# reflow.net
KiCad netlist of a schematic drawn in Altium Designer
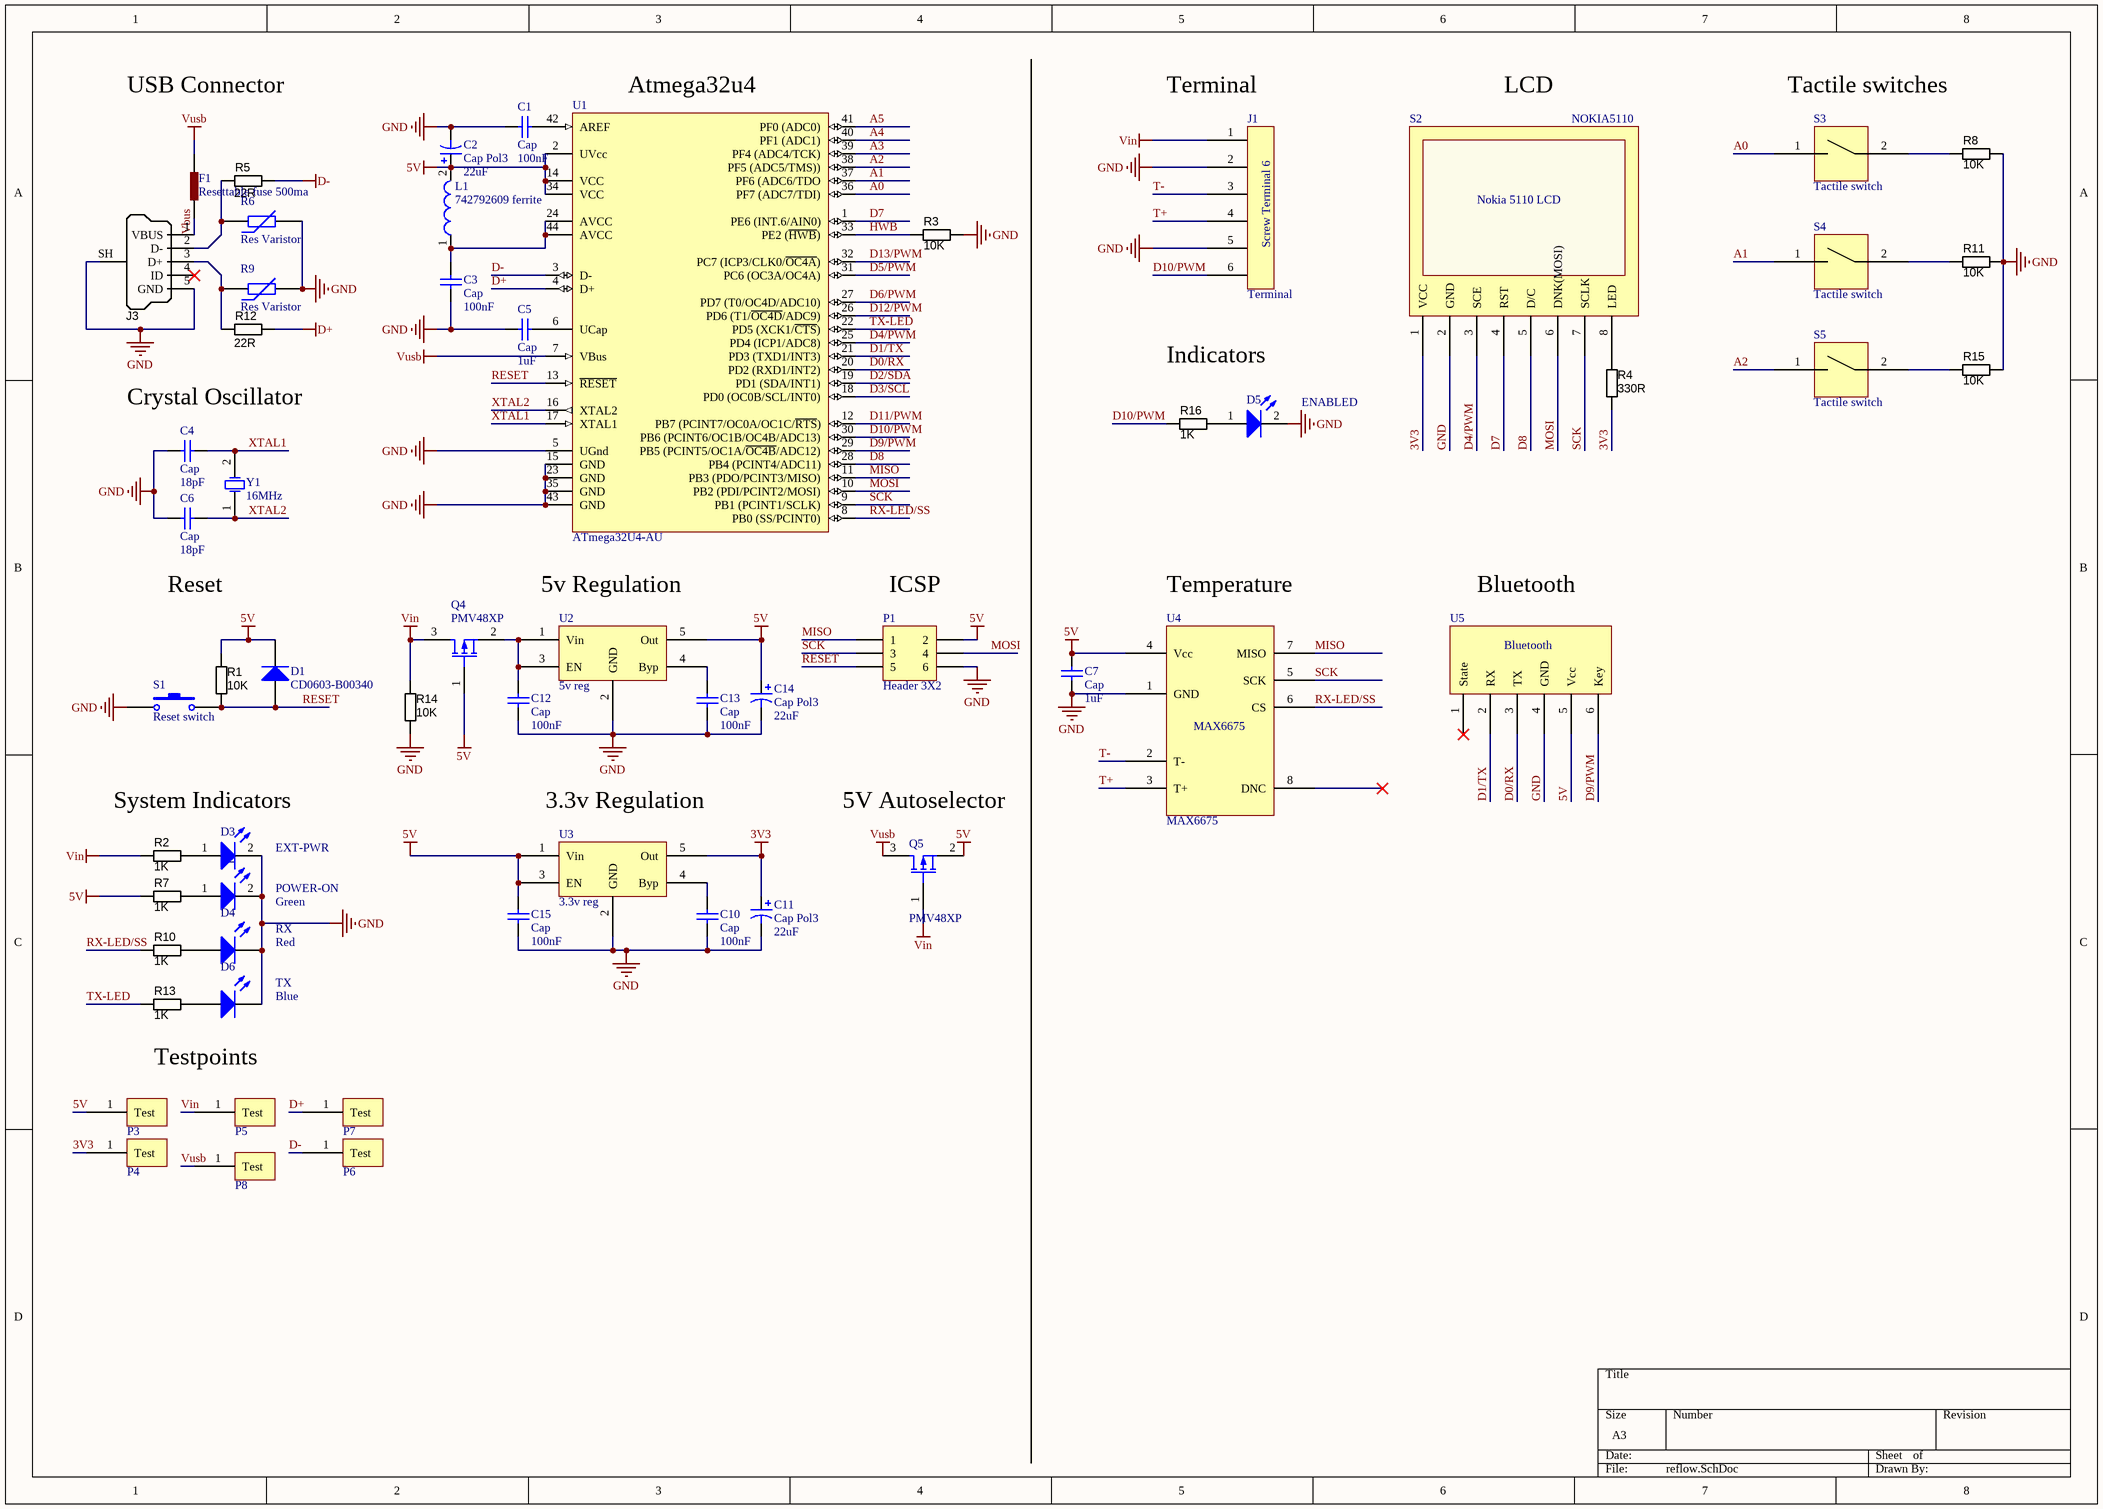
[diagram p0: reflow.SchDoc]

(export (version "E")
  (design (tool "Eeschema 10.0.6"))
  (components
    (comp (ref "C1")
      (value "Cap")
      (footprint "CAP-0603-GEN")
      (description "Capacitor")
      (fields (field (name "ALTIUM_VALUE") "100nF") (field (name "PUBLISHER") "Altium Limited"))
      (libsource (lib "Miscellaneous Devices") (part "Cap"))
    )
    (comp (ref "C2")
      (value "Cap Pol3")
      (footprint "CAP-0603-POL")
      (description "Polarized Capacitor (Surface Mount)")
      (fields (field (name "ALTIUM_VALUE") "22uF") (field (name "PUBLISHER") "Altium Limited"))
      (libsource (lib "Miscellaneous Devices") (part "Cap Pol3"))
    )
    (comp (ref "C3")
      (value "Cap")
      (footprint "CAP-0603-GEN")
      (description "Capacitor")
      (fields (field (name "ALTIUM_VALUE") "100nF") (field (name "PUBLISHER") "Altium Limited"))
      (libsource (lib "Miscellaneous Devices") (part "Cap"))
    )
    (comp (ref "C4")
      (value "Cap")
      (footprint "CAP-0603-GEN")
      (description "Capacitor")
      (fields (field (name "ALTIUM_VALUE") "18pF") (field (name "PUBLISHER") "Altium Limited"))
      (libsource (lib "Miscellaneous Devices") (part "Cap"))
    )
    (comp (ref "C5")
      (value "Cap")
      (footprint "CAP-0603-GEN")
      (description "Capacitor")
      (fields (field (name "ALTIUM_VALUE") "1uF") (field (name "PUBLISHER") "Altium Limited"))
      (libsource (lib "Miscellaneous Devices") (part "Cap"))
    )
    (comp (ref "C6")
      (value "Cap")
      (footprint "CAP-0603-GEN")
      (description "Capacitor")
      (fields (field (name "ALTIUM_VALUE") "18pF") (field (name "PUBLISHER") "Altium Limited"))
      (libsource (lib "Miscellaneous Devices") (part "Cap"))
    )
    (comp (ref "C7")
      (value "Cap")
      (footprint "CAP-0603-GEN")
      (description "Capacitor")
      (fields (field (name "ALTIUM_VALUE") "1uF") (field (name "PUBLISHER") "Altium Limited"))
      (libsource (lib "Miscellaneous Devices") (part "Cap"))
    )
    (comp (ref "C10")
      (value "Cap")
      (footprint "CAP-0603-GEN")
      (description "Capacitor")
      (fields (field (name "ALTIUM_VALUE") "100nF") (field (name "PUBLISHER") "Altium Limited"))
      (libsource (lib "Miscellaneous Devices") (part "Cap"))
    )
    (comp (ref "C11")
      (value "Cap Pol3")
      (footprint "CAP-0603-POL")
      (description "Polarized Capacitor (Surface Mount)")
      (fields (field (name "ALTIUM_VALUE") "22uF") (field (name "PUBLISHER") "Altium Limited"))
      (libsource (lib "Miscellaneous Devices") (part "Cap Pol3"))
    )
    (comp (ref "C12")
      (value "Cap")
      (footprint "CAP-0603-GEN")
      (description "Capacitor")
      (fields (field (name "ALTIUM_VALUE") "100nF") (field (name "PUBLISHER") "Altium Limited"))
      (libsource (lib "Miscellaneous Devices") (part "Cap"))
    )
    (comp (ref "C13")
      (value "Cap")
      (footprint "CAP-0603-GEN")
      (description "Capacitor")
      (fields (field (name "ALTIUM_VALUE") "100nF") (field (name "PUBLISHER") "Altium Limited"))
      (libsource (lib "Miscellaneous Devices") (part "Cap"))
    )
    (comp (ref "C14")
      (value "Cap Pol3")
      (footprint "CAP-0603-POL")
      (description "Polarized Capacitor (Surface Mount)")
      (fields (field (name "ALTIUM_VALUE") "22uF") (field (name "PUBLISHER") "Altium Limited"))
      (libsource (lib "Miscellaneous Devices") (part "Cap Pol3"))
    )
    (comp (ref "C15")
      (value "Cap")
      (footprint "CAP-0603-GEN")
      (description "Capacitor")
      (fields (field (name "ALTIUM_VALUE") "100nF") (field (name "PUBLISHER") "Altium Limited"))
      (libsource (lib "Miscellaneous Devices") (part "Cap"))
    )
    (comp (ref "D1")
      (value "CD0603-B00340")
      (footprint "DIODE-0603")
      (description "Default Diode")
      (fields (field (name "PUBLISHER") "Altium Limited"))
      (libsource (lib "Miscellaneous Devices") (part "Diode"))
    )
    (comp (ref "D2")
      (value "POWER-ON")
      (footprint "LED-0603")
      (description "Typical RED, GREEN, YELLOW, AMBER GaAs LED")
      (fields (field (name "PUBLISHER") "Altium Limited"))
      (libsource (lib "") (part "LED2_1"))
    )
    (comp (ref "D3")
      (value "EXT-PWR")
      (footprint "LED-0603")
      (description "Typical RED, GREEN, YELLOW, AMBER GaAs LED")
      (fields (field (name "PUBLISHER") "Altium Limited"))
      (libsource (lib "") (part "LED2_1"))
    )
    (comp (ref "D4")
      (value "RX")
      (footprint "LED-0603")
      (description "Typical RED, GREEN, YELLOW, AMBER GaAs LED")
      (fields (field (name "PUBLISHER") "Altium Limited"))
      (libsource (lib "Miscellaneous Devices") (part "LED2"))
    )
    (comp (ref "D5")
      (value "ENABLED")
      (footprint "LED-0603")
      (description "Typical RED, GREEN, YELLOW, AMBER GaAs LED")
      (fields (field (name "PUBLISHER") "Altium Limited"))
      (libsource (lib "") (part "LED2_1"))
    )
    (comp (ref "D6")
      (value "TX")
      (footprint "LED-0603")
      (description "Typical RED, GREEN, YELLOW, AMBER GaAs LED")
      (fields (field (name "PUBLISHER") "Altium Limited"))
      (libsource (lib "Miscellaneous Devices") (part "LED2"))
    )
    (comp (ref "F1")
      (value "Resettable fuse 500ma")
      (footprint "FUSE-0603")
      (description "Bourns resettable fuse")
      (libsource (lib "Bourns") (part "MF-MSMF"))
    )
    (comp (ref "J1")
      (value "Terminal")
      (footprint "HEADER-3x2-RIGHT")
      (description "Screw terminal")
      (libsource (lib "misc") (part "SCREW-TERMINAL-6"))
    )
    (comp (ref "J3")
      (value "USB Micro Type B (recommended if hand soldering)")
      (footprint "USB-MICRO-B")
      (description "Connector SMD-THD USB Micro Type B middle mount")
      (libsource (lib "PBL - Connectors") (part "USB_Micro_TypeB_FCI"))
    )
    (comp (ref "L1")
      (value "742792609 ferrite")
      (footprint "CAP-0603-GEN")
      (description "SMD EMI Suppression Ferrite Bead WE-CBF, Z = 30 Ohm")
      (libsource (lib "Wuerth Elektronik EMC Ferrite") (part "742792609"))
    )
    (comp (ref "P1")
      (value "Header 3X2")
      (footprint "TAG-CONNECT")
      (description "Header, 3-Pin, Dual row")
      (fields (field (name "PUBLISHER") "Altium Limited"))
      (libsource (lib "Miscellaneous Connectors") (part "Header 3X2"))
    )
    (comp (ref "P3") (value "TESTPOINT") (footprint "Testpoint") (libsource (lib "misc") (part "TESTPOINT")))
    (comp (ref "P4") (value "TESTPOINT") (footprint "Testpoint") (libsource (lib "misc") (part "TESTPOINT")))
    (comp (ref "P5") (value "TESTPOINT") (footprint "Testpoint") (libsource (lib "misc") (part "TESTPOINT")))
    (comp (ref "P6") (value "TESTPOINT") (footprint "Testpoint") (libsource (lib "misc") (part "TESTPOINT")))
    (comp (ref "P7") (value "TESTPOINT") (footprint "Testpoint") (libsource (lib "misc") (part "TESTPOINT")))
    (comp (ref "P8") (value "TESTPOINT") (footprint "Testpoint") (libsource (lib "misc") (part "TESTPOINT")))
    (comp (ref "Q4")
      (value "PMV48XP")
      (footprint "SOT23-3")
      (description "P-Channel MOSFET")
      (fields (field (name "PUBLISHER") "Altium Limited"))
      (libsource (lib "Miscellaneous Devices") (part "MOSFET-P"))
    )
    (comp (ref "Q5")
      (value "PMV48XP")
      (footprint "SOT23-3")
      (description "P-Channel MOSFET")
      (fields (field (name "PUBLISHER") "Altium Limited"))
      (libsource (lib "Miscellaneous Devices") (part "MOSFET-P"))
    )
    (comp (ref "R1")
      (value "10K")
      (footprint "RES-0603")
      (description "Resistor SMD chip 820 Ohm 0.1W 1% 0603")
      (fields (field (name "TOLERANCE") "±1%") (field (name "Comment") "Thick Film"))
      (libsource (lib "PBL - Resistors") (part "RES_820R_0603_1%"))
    )
    (comp (ref "R2")
      (value "1K")
      (footprint "RES-0603")
      (description "Resistor SMD chip 820 Ohm 0.1W 1% 0603")
      (fields (field (name "TOLERANCE") "±1%") (field (name "Comment") "Thick Film"))
      (libsource (lib "") (part "RES_820R_0603_1%_1"))
    )
    (comp (ref "R3")
      (value "10K")
      (footprint "RES-0603")
      (description "Resistor SMD chip 820 Ohm 0.1W 1% 0603")
      (fields (field (name "TOLERANCE") "±1%") (field (name "Comment") "Thick Film"))
      (libsource (lib "") (part "RES_820R_0603_1%_1"))
    )
    (comp (ref "R4")
      (value "330R")
      (footprint "RES-0603")
      (description "Resistor SMD chip 820 Ohm 0.1W 1% 0603")
      (fields (field (name "TOLERANCE") "±1%") (field (name "Comment") "Thick Film"))
      (libsource (lib "") (part "RES_820R_0603_1%_3"))
    )
    (comp (ref "R5")
      (value "22R")
      (footprint "RES-0603")
      (description "Resistor SMD chip 820 Ohm 0.1W 1% 0603")
      (fields (field (name "TOLERANCE") "±1%") (field (name "Comment") "Thick Film"))
      (libsource (lib "") (part "RES_820R_0603_1%_2"))
    )
    (comp (ref "R6")
      (value "Res Varistor")
      (footprint "RES-0603")
      (description "Varistor (Voltage-Sensitive Resistor)")
      (fields (field (name "PUBLISHER") "Altium Limited"))
      (libsource (lib "Miscellaneous Devices") (part "Res Varistor"))
    )
    (comp (ref "R7")
      (value "1K")
      (footprint "RES-0603")
      (description "Resistor SMD chip 820 Ohm 0.1W 1% 0603")
      (fields (field (name "TOLERANCE") "±1%") (field (name "Comment") "Thick Film"))
      (libsource (lib "") (part "RES_820R_0603_1%_1"))
    )
    (comp (ref "R8")
      (value "10K")
      (footprint "RES-0603")
      (description "Resistor SMD chip 820 Ohm 0.1W 1% 0603")
      (fields (field (name "TOLERANCE") "±1%") (field (name "Comment") "Thick Film"))
      (libsource (lib "") (part "RES_820R_0603_1%_1"))
    )
    (comp (ref "R9")
      (value "Res Varistor")
      (footprint "RES-0603")
      (description "Varistor (Voltage-Sensitive Resistor)")
      (fields (field (name "PUBLISHER") "Altium Limited"))
      (libsource (lib "Miscellaneous Devices") (part "Res Varistor"))
    )
    (comp (ref "R10")
      (value "1K")
      (footprint "RES-0603")
      (description "Resistor SMD chip 820 Ohm 0.1W 1% 0603")
      (fields (field (name "TOLERANCE") "±1%") (field (name "Comment") "Thick Film"))
      (libsource (lib "") (part "RES_820R_0603_1%_1"))
    )
    (comp (ref "R11")
      (value "10K")
      (footprint "RES-0603")
      (description "Resistor SMD chip 820 Ohm 0.1W 1% 0603")
      (fields (field (name "TOLERANCE") "±1%") (field (name "Comment") "Thick Film"))
      (libsource (lib "") (part "RES_820R_0603_1%_1"))
    )
    (comp (ref "R12")
      (value "22R")
      (footprint "RES-0603")
      (description "Resistor SMD chip 820 Ohm 0.1W 1% 0603")
      (fields (field (name "TOLERANCE") "±1%") (field (name "Comment") "Thick Film"))
      (libsource (lib "") (part "RES_820R_0603_1%_2"))
    )
    (comp (ref "R13")
      (value "1K")
      (footprint "RES-0603")
      (description "Resistor SMD chip 820 Ohm 0.1W 1% 0603")
      (fields (field (name "TOLERANCE") "±1%") (field (name "Comment") "Thick Film"))
      (libsource (lib "") (part "RES_820R_0603_1%_1"))
    )
    (comp (ref "R14")
      (value "10K")
      (footprint "RES-0603")
      (description "Resistor SMD chip 820 Ohm 0.1W 1% 0603")
      (fields (field (name "TOLERANCE") "±1%") (field (name "Comment") "Thick Film"))
      (libsource (lib "") (part "RES_820R_0603_1%_3"))
    )
    (comp (ref "R15")
      (value "10K")
      (footprint "RES-0603")
      (description "Resistor SMD chip 820 Ohm 0.1W 1% 0603")
      (fields (field (name "TOLERANCE") "±1%") (field (name "Comment") "Thick Film"))
      (libsource (lib "") (part "RES_820R_0603_1%_1"))
    )
    (comp (ref "R16")
      (value "1K")
      (footprint "RES-0603")
      (description "Resistor SMD chip 820 Ohm 0.1W 1% 0603")
      (fields (field (name "TOLERANCE") "±1%") (field (name "Comment") "Thick Film"))
      (libsource (lib "") (part "RES_820R_0603_1%_1"))
    )
    (comp (ref "S1")
      (value "Reset switch")
      (footprint "TACTILE-SWITCH")
      (description "Switch")
      (fields (field (name "PUBLISHER") "Altium Limited"))
      (libsource (lib "Miscellaneous Devices") (part "SW-PB"))
    )
    (comp (ref "S2") (value "NOKIA5110") (footprint "NOKIA5110") (libsource (lib "misc") (part "NOKIA5110")))
    (comp (ref "S3")
      (value "Tactile switch")
      (footprint "TACTILE-SWITCH")
      (libsource (lib "misc") (part "TACTILE-SWITCH-2"))
    )
    (comp (ref "S4")
      (value "Tactile switch")
      (footprint "TACTILE-SWITCH")
      (libsource (lib "misc") (part "TACTILE-SWITCH-2"))
    )
    (comp (ref "S5")
      (value "Tactile switch")
      (footprint "TACTILE-SWITCH")
      (libsource (lib "misc") (part "TACTILE-SWITCH-2"))
    )
    (comp (ref "U1")
      (value "ATmega32U4-AU")
      (footprint "44ML_N")
      (libsource (lib "Atmel Microcontroller megaAVR") (part "ATmega32U4-AU"))
    )
    (comp (ref "U2")
      (value "5v reg")
      (footprint "SOT23-5")
      (description "Voltage regulator")
      (libsource (lib "misc") (part "SOT23-REG"))
    )
    (comp (ref "U3")
      (value "3.3v reg")
      (footprint "SOT23-5")
      (description "Voltage regulator")
      (libsource (lib "misc") (part "SOT23-REG"))
    )
    (comp (ref "U4") (value "MAX6675") (footprint "SO8_N") (libsource (lib "misc") (part "MAX6675")))
    (comp (ref "U5")
      (value "Bluetooth module")
      (footprint "BLUETOOTH-MODULE")
      (libsource (lib "misc") (part "BLUETOOTH-MODULE"))
    )
    (comp (ref "Y1")
      (value "16MHz")
      (footprint "XTAL-5032")
      (description "Crystal Oscillator")
      (fields (field (name "PUBLISHER") "Altium Limited"))
      (libsource (lib "Miscellaneous Devices") (part "XTAL"))
    )
  )
  (nets
    (net (code "1") (name "/A0") (class "Default")
      (node (ref "S3") (pin "1") (pinfunction "1_1") (pintype "passive"))
      (node (ref "U1") (pin "36") (pinfunction "PF7_(ADC7/TDI)_36") (pintype "bidirectional"))
    )
    (net (code "2") (name "/A1") (class "Default")
      (node (ref "S4") (pin "1") (pinfunction "1_1") (pintype "passive"))
      (node (ref "U1") (pin "37") (pinfunction "PF6_(ADC6/TDO_37") (pintype "bidirectional"))
    )
    (net (code "3") (name "/A2") (class "Default")
      (node (ref "S5") (pin "1") (pinfunction "1_1") (pintype "passive"))
      (node (ref "U1") (pin "38") (pinfunction "PF5_(ADC5/TMS))_38") (pintype "bidirectional"))
    )
    (net (code "4") (name "/A3") (class "Default")
      (node (ref "U1") (pin "39") (pinfunction "PF4_(ADC4/TCK)_39") (pintype "bidirectional"))
    )
    (net (code "5") (name "/A4") (class "Default")
      (node (ref "U1") (pin "40") (pinfunction "PF1_(ADC1)_40") (pintype "bidirectional"))
    )
    (net (code "6") (name "/A5") (class "Default")
      (node (ref "U1") (pin "41") (pinfunction "PF0_(ADC0)_41") (pintype "bidirectional"))
    )
    (net (code "7") (name "/D0{slash}RX") (class "Default")
      (node (ref "U1") (pin "20") (pinfunction "PD2_(RXD1/INT2)_20") (pintype "bidirectional"))
      (node (ref "U5") (pin "3") (pinfunction "TX_3") (pintype "passive"))
    )
    (net (code "8") (name "/D1{slash}TX") (class "Default")
      (node (ref "U1") (pin "21") (pinfunction "PD3_(TXD1/INT3)_21") (pintype "bidirectional"))
      (node (ref "U5") (pin "2") (pinfunction "RX_2") (pintype "passive"))
    )
    (net (code "9") (name "/D2{slash}SDA") (class "Default")
      (node (ref "U1") (pin "19") (pinfunction "PD1_(SDA/INT1)_19") (pintype "bidirectional"))
    )
    (net (code "10") (name "/D3{slash}SCL") (class "Default")
      (node (ref "U1") (pin "18") (pinfunction "PD0_(OC0B/SCL/INT0)_18") (pintype "bidirectional"))
    )
    (net (code "11") (name "/D4{slash}PWM") (class "Default")
      (node (ref "S2") (pin "3") (pinfunction "SCE_3") (pintype "passive"))
      (node (ref "U1") (pin "25") (pinfunction "PD4_(ICP1/ADC8)_25") (pintype "bidirectional"))
    )
    (net (code "12") (name "/D5{slash}PWM") (class "Default")
      (node (ref "U1") (pin "31") (pinfunction "PC6_(OC3A/OC4A)_31") (pintype "bidirectional"))
    )
    (net (code "13") (name "/D6{slash}PWM") (class "Default")
      (node (ref "U1") (pin "27") (pinfunction "PD7_(T0/OC4D/ADC10)_27") (pintype "bidirectional"))
    )
    (net (code "14") (name "/D7") (class "Default")
      (node (ref "S2") (pin "4") (pinfunction "RST_4") (pintype "passive"))
      (node (ref "U1") (pin "1") (pinfunction "PE6_(INT.6/AIN0)_1") (pintype "bidirectional"))
    )
    (net (code "15") (name "/D8") (class "Default")
      (node (ref "S2") (pin "5") (pinfunction "D/C_5") (pintype "passive"))
      (node (ref "U1") (pin "28") (pinfunction "PB4_(PCINT4/ADC11)_28") (pintype "bidirectional"))
    )
    (net (code "16") (name "/D9{slash}PWM") (class "Default")
      (node (ref "U1") (pin "29") (pinfunction "PB5_(PCINT5/OC1A/~{OC4B}/ADC12)_29") (pintype "bidirectional"))
      (node (ref "U5") (pin "6") (pinfunction "Key_6") (pintype "passive"))
    )
    (net (code "17") (name "/D10{slash}PWM") (class "Default")
      (node (ref "J1") (pin "6") (pinfunction "6_6") (pintype "passive"))
      (node (ref "R16") (pin "2") (pinfunction "2_2") (pintype "passive"))
      (node (ref "U1") (pin "30") (pinfunction "PB6_(PCINT6/OC1B/OC4B/ADC13)_30") (pintype "bidirectional"))
    )
    (net (code "18") (name "/D11{slash}PWM") (class "Default")
      (node (ref "U1") (pin "12") (pinfunction "PB7_(PCINT7/OC0A/OC1C/~{RTS})_12") (pintype "bidirectional"))
    )
    (net (code "19") (name "/D12{slash}PWM") (class "Default")
      (node (ref "U1") (pin "26") (pinfunction "PD6_(T1/~{OC4D}/ADC9)_26") (pintype "bidirectional"))
    )
    (net (code "20") (name "/D13{slash}PWM") (class "Default")
      (node (ref "U1") (pin "32") (pinfunction "PC7_(ICP3/CLK0/~{OC4A})_32") (pintype "bidirectional"))
    )
    (net (code "21") (name "/HWB") (class "Default")
      (node (ref "R3") (pin "2") (pinfunction "2_2") (pintype "passive"))
      (node (ref "U1") (pin "33") (pinfunction "PE2_(~{HWB})_33") (pintype "bidirectional"))
    )
    (net (code "22") (name "/MISO") (class "Default")
      (node (ref "P1") (pin "1") (pinfunction "1_1") (pintype "passive"))
      (node (ref "U1") (pin "11") (pinfunction "PB3_(PDO/PCINT3/MISO)_11") (pintype "bidirectional"))
      (node (ref "U4") (pin "7") (pinfunction "MISO_7") (pintype "passive"))
    )
    (net (code "23") (name "/MOSI") (class "Default")
      (node (ref "P1") (pin "4") (pinfunction "4_4") (pintype "passive"))
      (node (ref "S2") (pin "6") (pinfunction "DNK(MOSI)_6") (pintype "passive"))
      (node (ref "U1") (pin "10") (pinfunction "PB2_(PDI/PCINT2/MOSI)_10") (pintype "bidirectional"))
    )
    (net (code "24") (name "/RESET") (class "Default")
      (node (ref "D1") (pin "1") (pinfunction "A_1") (pintype "passive"))
      (node (ref "P1") (pin "5") (pinfunction "5_5") (pintype "passive"))
      (node (ref "R1") (pin "1") (pinfunction "1_1") (pintype "passive"))
      (node (ref "S1") (pin "2") (pinfunction "2_2") (pintype "passive"))
      (node (ref "U1") (pin "13") (pinfunction "~{RESET}_13") (pintype "input"))
    )
    (net (code "25") (name "/RX-LED{slash}SS") (class "Default")
      (node (ref "R10") (pin "2") (pinfunction "2_2") (pintype "passive"))
      (node (ref "U1") (pin "8") (pinfunction "PB0_(SS/PCINT0)_8") (pintype "bidirectional"))
      (node (ref "U4") (pin "6") (pinfunction "CS_6") (pintype "passive"))
    )
    (net (code "26") (name "/SCK") (class "Default")
      (node (ref "P1") (pin "3") (pinfunction "3_3") (pintype "passive"))
      (node (ref "S2") (pin "7") (pinfunction "SCLK_7") (pintype "passive"))
      (node (ref "U1") (pin "9") (pinfunction "PB1_(PCINT1/SCLK)_9") (pintype "bidirectional"))
      (node (ref "U4") (pin "5") (pinfunction "SCK_5") (pintype "passive"))
    )
    (net (code "27") (name "/T+") (class "Default")
      (node (ref "J1") (pin "4") (pinfunction "4_4") (pintype "passive"))
      (node (ref "U4") (pin "3") (pinfunction "T+_3") (pintype "passive"))
    )
    (net (code "28") (name "/T-") (class "Default")
      (node (ref "J1") (pin "3") (pinfunction "3_3") (pintype "passive"))
      (node (ref "U4") (pin "2") (pinfunction "T-_2") (pintype "passive"))
    )
    (net (code "29") (name "/TX-LED") (class "Default")
      (node (ref "R13") (pin "2") (pinfunction "2_2") (pintype "passive"))
      (node (ref "U1") (pin "22") (pinfunction "PD5_(XCK1/~{CTS})_22") (pintype "bidirectional"))
    )
    (net (code "30") (name "/Vbus") (class "Default")
      (node (ref "F1") (pin "1") (pinfunction "1_1") (pintype "passive"))
      (node (ref "J3") (pin "1") (pinfunction "VBUS_1") (pintype "passive"))
    )
    (net (code "31") (name "/XTAL1") (class "Default")
      (node (ref "C4") (pin "1") (pinfunction "1_1") (pintype "passive"))
      (node (ref "U1") (pin "17") (pinfunction "XTAL1_17") (pintype "input"))
      (node (ref "Y1") (pin "2") (pinfunction "OSC2_2") (pintype "passive"))
    )
    (net (code "32") (name "/XTAL2") (class "Default")
      (node (ref "C6") (pin "1") (pinfunction "1_1") (pintype "passive"))
      (node (ref "U1") (pin "16") (pinfunction "XTAL2_16") (pintype "output"))
      (node (ref "Y1") (pin "1") (pinfunction "OSC1_1") (pintype "passive"))
    )
    (net (code "33") (name "3V3") (class "Default")
      (node (ref "C11") (pin "1") (pinfunction "1_1") (pintype "passive"))
      (node (ref "P4") (pin "1") (pinfunction "Test_1") (pintype "passive"))
      (node (ref "R4") (pin "2") (pinfunction "2_2") (pintype "passive"))
      (node (ref "S2") (pin "1") (pinfunction "VCC_1") (pintype "passive"))
      (node (ref "U3") (pin "5") (pinfunction "Out_5") (pintype "passive"))
    )
    (net (code "34") (name "5V") (class "Default")
      (node (ref "C14") (pin "1") (pinfunction "1_1") (pintype "passive"))
      (node (ref "C15") (pin "2") (pinfunction "2_2") (pintype "passive"))
      (node (ref "C2") (pin "1") (pinfunction "1_1") (pintype "passive"))
      (node (ref "C7") (pin "2") (pinfunction "2_2") (pintype "passive"))
      (node (ref "D1") (pin "2") (pinfunction "K_2") (pintype "passive"))
      (node (ref "L1") (pin "2") (pinfunction "2_2") (pintype "passive"))
      (node (ref "P1") (pin "2") (pinfunction "2_2") (pintype "passive"))
      (node (ref "P3") (pin "1") (pinfunction "Test_1") (pintype "passive"))
      (node (ref "Q4") (pin "1") (pinfunction "S_1") (pintype "passive"))
      (node (ref "Q5") (pin "2") (pinfunction "D_2") (pintype "passive"))
      (node (ref "R1") (pin "2") (pinfunction "2_2") (pintype "passive"))
      (node (ref "R7") (pin "2") (pinfunction "2_2") (pintype "passive"))
      (node (ref "U1") (pin "14") (pinfunction "VCC_14") (pintype "power_in"))
      (node (ref "U1") (pin "2") (pinfunction "UVcc_2") (pintype "power_in"))
      (node (ref "U1") (pin "34") (pinfunction "VCC_34") (pintype "power_in"))
      (node (ref "U2") (pin "5") (pinfunction "Out_5") (pintype "passive"))
      (node (ref "U3") (pin "1") (pinfunction "Vin_1") (pintype "passive"))
      (node (ref "U3") (pin "3") (pinfunction "EN_3") (pintype "passive"))
      (node (ref "U4") (pin "4") (pinfunction "Vcc_4") (pintype "passive"))
      (node (ref "U5") (pin "5") (pinfunction "Vcc_5") (pintype "passive"))
    )
    (net (code "35") (name "D+") (class "Default")
      (node (ref "P7") (pin "1") (pinfunction "Test_1") (pintype "passive"))
      (node (ref "R12") (pin "2") (pinfunction "2_2") (pintype "passive"))
      (node (ref "U1") (pin "4") (pinfunction "D+_4") (pintype "bidirectional"))
    )
    (net (code "36") (name "D-") (class "Default")
      (node (ref "P6") (pin "1") (pinfunction "Test_1") (pintype "passive"))
      (node (ref "R5") (pin "2") (pinfunction "2_2") (pintype "passive"))
      (node (ref "U1") (pin "3") (pinfunction "D-_3") (pintype "bidirectional"))
    )
    (net (code "37") (name "GND") (class "Default")
      (node (ref "C1") (pin "2") (pinfunction "2_2") (pintype "passive"))
      (node (ref "C10") (pin "1") (pinfunction "1_1") (pintype "passive"))
      (node (ref "C11") (pin "2") (pinfunction "2_2") (pintype "passive"))
      (node (ref "C12") (pin "1") (pinfunction "1_1") (pintype "passive"))
      (node (ref "C13") (pin "1") (pinfunction "1_1") (pintype "passive"))
      (node (ref "C14") (pin "2") (pinfunction "2_2") (pintype "passive"))
      (node (ref "C15") (pin "1") (pinfunction "1_1") (pintype "passive"))
      (node (ref "C2") (pin "2") (pinfunction "2_2") (pintype "passive"))
      (node (ref "C3") (pin "1") (pinfunction "1_1") (pintype "passive"))
      (node (ref "C4") (pin "2") (pinfunction "2_2") (pintype "passive"))
      (node (ref "C5") (pin "2") (pinfunction "2_2") (pintype "passive"))
      (node (ref "C6") (pin "2") (pinfunction "2_2") (pintype "passive"))
      (node (ref "C7") (pin "1") (pinfunction "1_1") (pintype "passive"))
      (node (ref "D2") (pin "2") (pinfunction "K_2") (pintype "passive"))
      (node (ref "D3") (pin "2") (pinfunction "K_2") (pintype "passive"))
      (node (ref "D4") (pin "2") (pinfunction "K_2") (pintype "passive"))
      (node (ref "D5") (pin "2") (pinfunction "K_2") (pintype "passive"))
      (node (ref "D6") (pin "2") (pinfunction "K_2") (pintype "passive"))
      (node (ref "J1") (pin "2") (pinfunction "2_2") (pintype "passive"))
      (node (ref "J1") (pin "5") (pinfunction "5_5") (pintype "passive"))
      (node (ref "J3") (pin "5") (pinfunction "GND_5") (pintype "passive"))
      (node (ref "J3") (pin "SH") (pinfunction "Shell_SH") (pintype "passive"))
      (node (ref "P1") (pin "6") (pinfunction "6_6") (pintype "passive"))
      (node (ref "R11") (pin "1") (pinfunction "1_1") (pintype "passive"))
      (node (ref "R14") (pin "2") (pinfunction "2_2") (pintype "passive"))
      (node (ref "R15") (pin "1") (pinfunction "1_1") (pintype "passive"))
      (node (ref "R3") (pin "1") (pinfunction "1_1") (pintype "passive"))
      (node (ref "R6") (pin "2") (pinfunction "2_2") (pintype "passive"))
      (node (ref "R8") (pin "1") (pinfunction "1_1") (pintype "passive"))
      (node (ref "R9") (pin "2") (pinfunction "2_2") (pintype "passive"))
      (node (ref "S1") (pin "1") (pinfunction "1_1") (pintype "passive"))
      (node (ref "S2") (pin "2") (pinfunction "GND_2") (pintype "passive"))
      (node (ref "U1") (pin "15") (pinfunction "GND_15") (pintype "power_in"))
      (node (ref "U1") (pin "23") (pinfunction "GND_23") (pintype "power_in"))
      (node (ref "U1") (pin "35") (pinfunction "GND_35") (pintype "power_in"))
      (node (ref "U1") (pin "43") (pinfunction "GND_43") (pintype "power_in"))
      (node (ref "U1") (pin "5") (pinfunction "UGnd_5") (pintype "power_in"))
      (node (ref "U2") (pin "2") (pinfunction "GND_2") (pintype "passive"))
      (node (ref "U3") (pin "2") (pinfunction "GND_2") (pintype "passive"))
      (node (ref "U4") (pin "1") (pinfunction "GND_1") (pintype "passive"))
      (node (ref "U5") (pin "4") (pinfunction "GND_4") (pintype "passive"))
    )
    (net (code "38") (name "Net-(C3-Pad2)") (class "Default")
      (node (ref "C3") (pin "2") (pinfunction "2_2") (pintype "passive"))
      (node (ref "L1") (pin "1") (pinfunction "1_1") (pintype "passive"))
      (node (ref "U1") (pin "24") (pinfunction "AVCC_24") (pintype "power_in"))
      (node (ref "U1") (pin "44") (pinfunction "AVCC_44") (pintype "power_in"))
    )
    (net (code "39") (name "Net-(D2-A)") (class "Default")
      (node (ref "D2") (pin "1") (pinfunction "A_1") (pintype "passive"))
      (node (ref "R7") (pin "1") (pinfunction "1_1") (pintype "passive"))
    )
    (net (code "40") (name "Net-(D3-A)") (class "Default")
      (node (ref "D3") (pin "1") (pinfunction "A_1") (pintype "passive"))
      (node (ref "R2") (pin "1") (pinfunction "1_1") (pintype "passive"))
    )
    (net (code "41") (name "Net-(D4-A)") (class "Default")
      (node (ref "D4") (pin "1") (pinfunction "A_1") (pintype "passive"))
      (node (ref "R10") (pin "1") (pinfunction "1_1") (pintype "passive"))
    )
    (net (code "42") (name "Net-(D5-A)") (class "Default")
      (node (ref "D5") (pin "1") (pinfunction "A_1") (pintype "passive"))
      (node (ref "R16") (pin "1") (pinfunction "1_1") (pintype "passive"))
    )
    (net (code "43") (name "Net-(D6-A)") (class "Default")
      (node (ref "D6") (pin "1") (pinfunction "A_1") (pintype "passive"))
      (node (ref "R13") (pin "1") (pinfunction "1_1") (pintype "passive"))
    )
    (net (code "44") (name "Net-(J3-D+)") (class "Default")
      (node (ref "J3") (pin "3") (pinfunction "D+_3") (pintype "passive"))
      (node (ref "R12") (pin "1") (pinfunction "1_1") (pintype "passive"))
      (node (ref "R9") (pin "1") (pinfunction "1_1") (pintype "passive"))
    )
    (net (code "45") (name "Net-(J3-D-)") (class "Default")
      (node (ref "J3") (pin "2") (pinfunction "D-_2") (pintype "passive"))
      (node (ref "R5") (pin "1") (pinfunction "1_1") (pintype "passive"))
      (node (ref "R6") (pin "1") (pinfunction "1_1") (pintype "passive"))
    )
    (net (code "46") (name "Net-(Q4-D)") (class "Default")
      (node (ref "C12") (pin "2") (pinfunction "2_2") (pintype "passive"))
      (node (ref "Q4") (pin "2") (pinfunction "D_2") (pintype "passive"))
      (node (ref "U2") (pin "1") (pinfunction "Vin_1") (pintype "passive"))
      (node (ref "U2") (pin "3") (pinfunction "EN_3") (pintype "passive"))
    )
    (net (code "47") (name "Net-(R8-Pad2)") (class "Default")
      (node (ref "R8") (pin "2") (pinfunction "2_2") (pintype "passive"))
      (node (ref "S3") (pin "2") (pinfunction "2_2") (pintype "passive"))
    )
    (net (code "48") (name "Net-(R11-Pad2)") (class "Default")
      (node (ref "R11") (pin "2") (pinfunction "2_2") (pintype "passive"))
      (node (ref "S4") (pin "2") (pinfunction "2_2") (pintype "passive"))
    )
    (net (code "49") (name "Net-(R15-Pad2)") (class "Default")
      (node (ref "R15") (pin "2") (pinfunction "2_2") (pintype "passive"))
      (node (ref "S5") (pin "2") (pinfunction "2_2") (pintype "passive"))
    )
    (net (code "50") (name "Net-(S2-LED)") (class "Default")
      (node (ref "R4") (pin "1") (pinfunction "1_1") (pintype "passive"))
      (node (ref "S2") (pin "8") (pinfunction "LED_8") (pintype "passive"))
    )
    (net (code "51") (name "Net-(U1-AREF)") (class "Default")
      (node (ref "C1") (pin "1") (pinfunction "1_1") (pintype "passive"))
      (node (ref "U1") (pin "42") (pinfunction "AREF_42") (pintype "input"))
    )
    (net (code "52") (name "Net-(U1-UCap)") (class "Default")
      (node (ref "C5") (pin "1") (pinfunction "1_1") (pintype "passive"))
      (node (ref "U1") (pin "6") (pinfunction "UCap_6") (pintype "passive"))
    )
    (net (code "53") (name "Net-(U2-Byp)") (class "Default")
      (node (ref "C13") (pin "2") (pinfunction "2_2") (pintype "passive"))
      (node (ref "U2") (pin "4") (pinfunction "Byp_4") (pintype "passive"))
    )
    (net (code "54") (name "Net-(U3-Byp)") (class "Default")
      (node (ref "C10") (pin "2") (pinfunction "2_2") (pintype "passive"))
      (node (ref "U3") (pin "4") (pinfunction "Byp_4") (pintype "passive"))
    )
    (net (code "55") (name "Vin") (class "Default")
      (node (ref "J1") (pin "1") (pinfunction "1_1") (pintype "passive"))
      (node (ref "P5") (pin "1") (pinfunction "Test_1") (pintype "passive"))
      (node (ref "Q4") (pin "3") (pinfunction "G_3") (pintype "passive"))
      (node (ref "Q5") (pin "1") (pinfunction "S_1") (pintype "passive"))
      (node (ref "R14") (pin "1") (pinfunction "1_1") (pintype "passive"))
      (node (ref "R2") (pin "2") (pinfunction "2_2") (pintype "passive"))
    )
    (net (code "56") (name "Vusb") (class "Default")
      (node (ref "F1") (pin "0") (pinfunction "0_0") (pintype "passive"))
      (node (ref "P8") (pin "1") (pinfunction "Test_1") (pintype "passive"))
      (node (ref "Q5") (pin "3") (pinfunction "G_3") (pintype "passive"))
      (node (ref "U1") (pin "7") (pinfunction "VBus_7") (pintype "input"))
    )
    (net (code "57") (name "unconnected-(J3-ID-Pad4)") (class "Default")
      (node (ref "J3") (pin "4") (pinfunction "ID_4") (pintype "passive+no_connect"))
    )
    (net (code "58") (name "unconnected-(U4-DNC-Pad8)") (class "Default")
      (node (ref "U4") (pin "8") (pinfunction "DNC_8") (pintype "passive+no_connect"))
    )
    (net (code "59") (name "unconnected-(U5-State-Pad1)") (class "Default")
      (node (ref "U5") (pin "1") (pinfunction "State_1") (pintype "passive+no_connect"))
    )
  )
)
